# Arduino_DUE_Shield.net
KiCad netlist of a schematic drawn in EAGLE
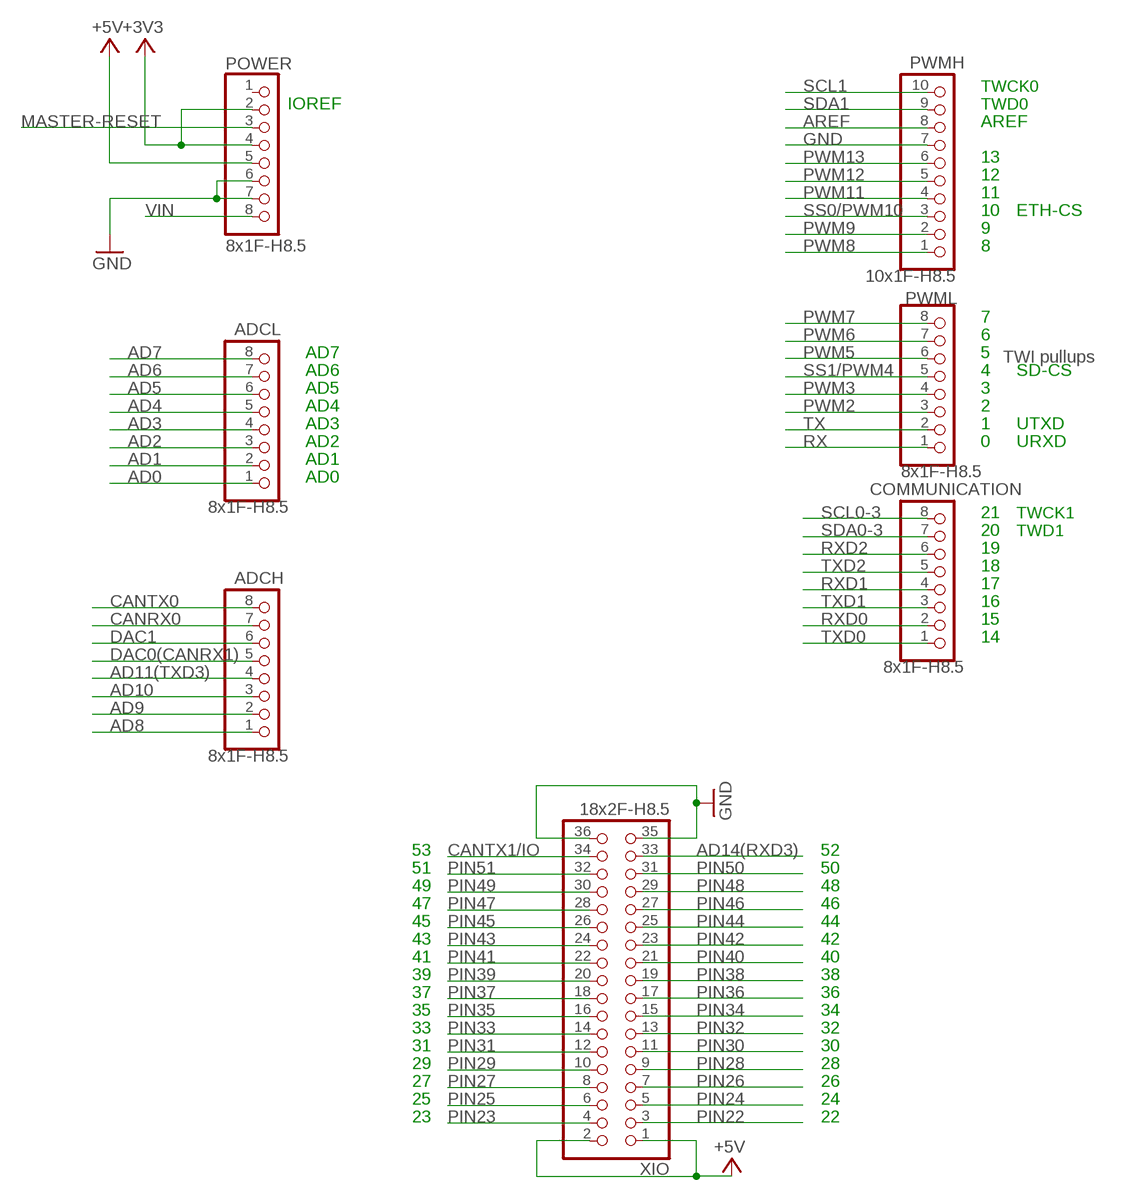
[diagram p0: schematic, sheet 1]

(export (version "E")
  (design (tool "Eeschema 10.0.6"))
  (components
    (comp (ref "ADCH")
      (value "8x1F-H8.5")
      (footprint "eagle-import:1X08")
      (libsource (lib "eagle-import") (part "PINHD-1X8"))
    )
    (comp (ref "ADCL")
      (value "8x1F-H8.5")
      (footprint "eagle-import:1X08")
      (libsource (lib "eagle-import") (part "PINHD-1X8"))
    )
    (comp (ref "COMMUNICATION")
      (value "8x1F-H8.5")
      (footprint "eagle-import:1X08")
      (libsource (lib "eagle-import") (part "PINHD-1X8"))
    )
    (comp (ref "POWER")
      (value "8x1F-H8.5")
      (footprint "eagle-import:1X08")
      (libsource (lib "eagle-import") (part "PINHD-1X8"))
    )
    (comp (ref "PWMH")
      (value "10x1F-H8.5")
      (footprint "eagle-import:1X10")
      (libsource (lib "eagle-import") (part "PINHD-1X10"))
    )
    (comp (ref "PWML")
      (value "8x1F-H8.5")
      (footprint "eagle-import:1X08")
      (libsource (lib "eagle-import") (part "PINHD-1X8"))
    )
    (comp (ref "XIO")
      (value "18x2F-H8.5")
      (footprint "eagle-import:2X18")
      (libsource (lib "eagle-import") (part "PINHD-2X18"))
    )
  )
  (nets
    (net (code "1") (name "+3V3") (class "Default")
      (node (ref "POWER") (pin "2") (pinfunction "2_2") (pintype "passive"))
      (node (ref "POWER") (pin "4") (pinfunction "4_4") (pintype "passive"))
    )
    (net (code "2") (name "+5V") (class "Default")
      (node (ref "POWER") (pin "5") (pinfunction "5_5") (pintype "passive"))
      (node (ref "XIO") (pin "1") (pinfunction "1_1") (pintype "passive"))
      (node (ref "XIO") (pin "2") (pinfunction "2_2") (pintype "passive"))
    )
    (net (code "3") (name "/AD0") (class "Default")
      (node (ref "ADCL") (pin "1") (pinfunction "1_1") (pintype "passive"))
    )
    (net (code "4") (name "/AD1") (class "Default")
      (node (ref "ADCL") (pin "2") (pinfunction "2_2") (pintype "passive"))
    )
    (net (code "5") (name "/AD2") (class "Default")
      (node (ref "ADCL") (pin "3") (pinfunction "3_3") (pintype "passive"))
    )
    (net (code "6") (name "/AD3") (class "Default")
      (node (ref "ADCL") (pin "4") (pinfunction "4_4") (pintype "passive"))
    )
    (net (code "7") (name "/AD4") (class "Default")
      (node (ref "ADCL") (pin "5") (pinfunction "5_5") (pintype "passive"))
    )
    (net (code "8") (name "/AD5") (class "Default")
      (node (ref "ADCL") (pin "6") (pinfunction "6_6") (pintype "passive"))
    )
    (net (code "9") (name "/AD6") (class "Default")
      (node (ref "ADCL") (pin "7") (pinfunction "7_7") (pintype "passive"))
    )
    (net (code "10") (name "/AD7") (class "Default")
      (node (ref "ADCL") (pin "8") (pinfunction "8_8") (pintype "passive"))
    )
    (net (code "11") (name "/AD8") (class "Default")
      (node (ref "ADCH") (pin "1") (pinfunction "1_1") (pintype "passive"))
    )
    (net (code "12") (name "/AD9") (class "Default")
      (node (ref "ADCH") (pin "2") (pinfunction "2_2") (pintype "passive"))
    )
    (net (code "13") (name "/AD10") (class "Default")
      (node (ref "ADCH") (pin "3") (pinfunction "3_3") (pintype "passive"))
    )
    (net (code "14") (name "/AD11(TXD3)") (class "Default")
      (node (ref "ADCH") (pin "4") (pinfunction "4_4") (pintype "passive"))
    )
    (net (code "15") (name "/AD14(RXD3)") (class "Default")
      (node (ref "XIO") (pin "33") (pinfunction "33_33") (pintype "passive"))
    )
    (net (code "16") (name "/AREF") (class "Default")
      (node (ref "PWMH") (pin "8") (pinfunction "8_8") (pintype "passive"))
    )
    (net (code "17") (name "/CANRX0") (class "Default")
      (node (ref "ADCH") (pin "7") (pinfunction "7_7") (pintype "passive"))
    )
    (net (code "18") (name "/CANTX0") (class "Default")
      (node (ref "ADCH") (pin "8") (pinfunction "8_8") (pintype "passive"))
    )
    (net (code "19") (name "/CANTX1{slash}IO") (class "Default")
      (node (ref "XIO") (pin "34") (pinfunction "34_34") (pintype "passive"))
    )
    (net (code "20") (name "/DAC0(CANRX1)") (class "Default")
      (node (ref "ADCH") (pin "5") (pinfunction "5_5") (pintype "passive"))
    )
    (net (code "21") (name "/DAC1") (class "Default")
      (node (ref "ADCH") (pin "6") (pinfunction "6_6") (pintype "passive"))
    )
    (net (code "22") (name "/MASTER-RESET") (class "Default")
      (node (ref "POWER") (pin "3") (pinfunction "3_3") (pintype "passive"))
    )
    (net (code "23") (name "/PIN22") (class "Default")
      (node (ref "XIO") (pin "3") (pinfunction "3_3") (pintype "passive"))
    )
    (net (code "24") (name "/PIN23") (class "Default")
      (node (ref "XIO") (pin "4") (pinfunction "4_4") (pintype "passive"))
    )
    (net (code "25") (name "/PIN24") (class "Default")
      (node (ref "XIO") (pin "5") (pinfunction "5_5") (pintype "passive"))
    )
    (net (code "26") (name "/PIN25") (class "Default")
      (node (ref "XIO") (pin "6") (pinfunction "6_6") (pintype "passive"))
    )
    (net (code "27") (name "/PIN26") (class "Default")
      (node (ref "XIO") (pin "7") (pinfunction "7_7") (pintype "passive"))
    )
    (net (code "28") (name "/PIN27") (class "Default")
      (node (ref "XIO") (pin "8") (pinfunction "8_8") (pintype "passive"))
    )
    (net (code "29") (name "/PIN28") (class "Default")
      (node (ref "XIO") (pin "9") (pinfunction "9_9") (pintype "passive"))
    )
    (net (code "30") (name "/PIN29") (class "Default")
      (node (ref "XIO") (pin "10") (pinfunction "10_10") (pintype "passive"))
    )
    (net (code "31") (name "/PIN30") (class "Default")
      (node (ref "XIO") (pin "11") (pinfunction "11_11") (pintype "passive"))
    )
    (net (code "32") (name "/PIN31") (class "Default")
      (node (ref "XIO") (pin "12") (pinfunction "12_12") (pintype "passive"))
    )
    (net (code "33") (name "/PIN32") (class "Default")
      (node (ref "XIO") (pin "13") (pinfunction "13_13") (pintype "passive"))
    )
    (net (code "34") (name "/PIN33") (class "Default")
      (node (ref "XIO") (pin "14") (pinfunction "14_14") (pintype "passive"))
    )
    (net (code "35") (name "/PIN34") (class "Default")
      (node (ref "XIO") (pin "15") (pinfunction "15_15") (pintype "passive"))
    )
    (net (code "36") (name "/PIN35") (class "Default")
      (node (ref "XIO") (pin "16") (pinfunction "16_16") (pintype "passive"))
    )
    (net (code "37") (name "/PIN36") (class "Default")
      (node (ref "XIO") (pin "17") (pinfunction "17_17") (pintype "passive"))
    )
    (net (code "38") (name "/PIN37") (class "Default")
      (node (ref "XIO") (pin "18") (pinfunction "18_18") (pintype "passive"))
    )
    (net (code "39") (name "/PIN38") (class "Default")
      (node (ref "XIO") (pin "19") (pinfunction "19_19") (pintype "passive"))
    )
    (net (code "40") (name "/PIN39") (class "Default")
      (node (ref "XIO") (pin "20") (pinfunction "20_20") (pintype "passive"))
    )
    (net (code "41") (name "/PIN40") (class "Default")
      (node (ref "XIO") (pin "21") (pinfunction "21_21") (pintype "passive"))
    )
    (net (code "42") (name "/PIN41") (class "Default")
      (node (ref "XIO") (pin "22") (pinfunction "22_22") (pintype "passive"))
    )
    (net (code "43") (name "/PIN42") (class "Default")
      (node (ref "XIO") (pin "23") (pinfunction "23_23") (pintype "passive"))
    )
    (net (code "44") (name "/PIN43") (class "Default")
      (node (ref "XIO") (pin "24") (pinfunction "24_24") (pintype "passive"))
    )
    (net (code "45") (name "/PIN44") (class "Default")
      (node (ref "XIO") (pin "25") (pinfunction "25_25") (pintype "passive"))
    )
    (net (code "46") (name "/PIN45") (class "Default")
      (node (ref "XIO") (pin "26") (pinfunction "26_26") (pintype "passive"))
    )
    (net (code "47") (name "/PIN46") (class "Default")
      (node (ref "XIO") (pin "27") (pinfunction "27_27") (pintype "passive"))
    )
    (net (code "48") (name "/PIN47") (class "Default")
      (node (ref "XIO") (pin "28") (pinfunction "28_28") (pintype "passive"))
    )
    (net (code "49") (name "/PIN48") (class "Default")
      (node (ref "XIO") (pin "29") (pinfunction "29_29") (pintype "passive"))
    )
    (net (code "50") (name "/PIN49") (class "Default")
      (node (ref "XIO") (pin "30") (pinfunction "30_30") (pintype "passive"))
    )
    (net (code "51") (name "/PIN50") (class "Default")
      (node (ref "XIO") (pin "31") (pinfunction "31_31") (pintype "passive"))
    )
    (net (code "52") (name "/PIN51") (class "Default")
      (node (ref "XIO") (pin "32") (pinfunction "32_32") (pintype "passive"))
    )
    (net (code "53") (name "/PWM2") (class "Default")
      (node (ref "PWML") (pin "3") (pinfunction "3_3") (pintype "passive"))
    )
    (net (code "54") (name "/PWM3") (class "Default")
      (node (ref "PWML") (pin "4") (pinfunction "4_4") (pintype "passive"))
    )
    (net (code "55") (name "/PWM5") (class "Default")
      (node (ref "PWML") (pin "6") (pinfunction "6_6") (pintype "passive"))
    )
    (net (code "56") (name "/PWM6") (class "Default")
      (node (ref "PWML") (pin "7") (pinfunction "7_7") (pintype "passive"))
    )
    (net (code "57") (name "/PWM7") (class "Default")
      (node (ref "PWML") (pin "8") (pinfunction "8_8") (pintype "passive"))
    )
    (net (code "58") (name "/PWM8") (class "Default")
      (node (ref "PWMH") (pin "1") (pinfunction "1_1") (pintype "passive"))
    )
    (net (code "59") (name "/PWM9") (class "Default")
      (node (ref "PWMH") (pin "2") (pinfunction "2_2") (pintype "passive"))
    )
    (net (code "60") (name "/PWM11") (class "Default")
      (node (ref "PWMH") (pin "4") (pinfunction "4_4") (pintype "passive"))
    )
    (net (code "61") (name "/PWM12") (class "Default")
      (node (ref "PWMH") (pin "5") (pinfunction "5_5") (pintype "passive"))
    )
    (net (code "62") (name "/PWM13") (class "Default")
      (node (ref "PWMH") (pin "6") (pinfunction "6_6") (pintype "passive"))
    )
    (net (code "63") (name "/RX") (class "Default")
      (node (ref "PWML") (pin "1") (pinfunction "1_1") (pintype "passive"))
    )
    (net (code "64") (name "/RXD0") (class "Default")
      (node (ref "COMMUNICATION") (pin "2") (pinfunction "2_2") (pintype "passive"))
    )
    (net (code "65") (name "/RXD1") (class "Default")
      (node (ref "COMMUNICATION") (pin "4") (pinfunction "4_4") (pintype "passive"))
    )
    (net (code "66") (name "/RXD2") (class "Default")
      (node (ref "COMMUNICATION") (pin "6") (pinfunction "6_6") (pintype "passive"))
    )
    (net (code "67") (name "/SCL0-3") (class "Default")
      (node (ref "COMMUNICATION") (pin "8") (pinfunction "8_8") (pintype "passive"))
    )
    (net (code "68") (name "/SCL1") (class "Default")
      (node (ref "PWMH") (pin "10") (pinfunction "10_10") (pintype "passive"))
    )
    (net (code "69") (name "/SDA0-3") (class "Default")
      (node (ref "COMMUNICATION") (pin "7") (pinfunction "7_7") (pintype "passive"))
    )
    (net (code "70") (name "/SDA1") (class "Default")
      (node (ref "PWMH") (pin "9") (pinfunction "9_9") (pintype "passive"))
    )
    (net (code "71") (name "/SS0{slash}PWM10") (class "Default")
      (node (ref "PWMH") (pin "3") (pinfunction "3_3") (pintype "passive"))
    )
    (net (code "72") (name "/SS1{slash}PWM4") (class "Default")
      (node (ref "PWML") (pin "5") (pinfunction "5_5") (pintype "passive"))
    )
    (net (code "73") (name "/TX") (class "Default")
      (node (ref "PWML") (pin "2") (pinfunction "2_2") (pintype "passive"))
    )
    (net (code "74") (name "/TXD0") (class "Default")
      (node (ref "COMMUNICATION") (pin "1") (pinfunction "1_1") (pintype "passive"))
    )
    (net (code "75") (name "/TXD1") (class "Default")
      (node (ref "COMMUNICATION") (pin "3") (pinfunction "3_3") (pintype "passive"))
    )
    (net (code "76") (name "/TXD2") (class "Default")
      (node (ref "COMMUNICATION") (pin "5") (pinfunction "5_5") (pintype "passive"))
    )
    (net (code "77") (name "/VIN") (class "Default")
      (node (ref "POWER") (pin "8") (pinfunction "8_8") (pintype "passive"))
    )
    (net (code "78") (name "GND") (class "Default")
      (node (ref "POWER") (pin "6") (pinfunction "6_6") (pintype "passive"))
      (node (ref "POWER") (pin "7") (pinfunction "7_7") (pintype "passive"))
      (node (ref "PWMH") (pin "7") (pinfunction "7_7") (pintype "passive"))
      (node (ref "XIO") (pin "35") (pinfunction "35_35") (pintype "passive"))
      (node (ref "XIO") (pin "36") (pinfunction "36_36") (pintype "passive"))
    )
    (net (code "79") (name "unconnected-(POWER-Pad1)") (class "Default")
      (node (ref "POWER") (pin "1") (pinfunction "1_1") (pintype "passive"))
    )
  )
)
